# Gate_Drive.net
KiCad netlist of a schematic drawn in Altium Designer
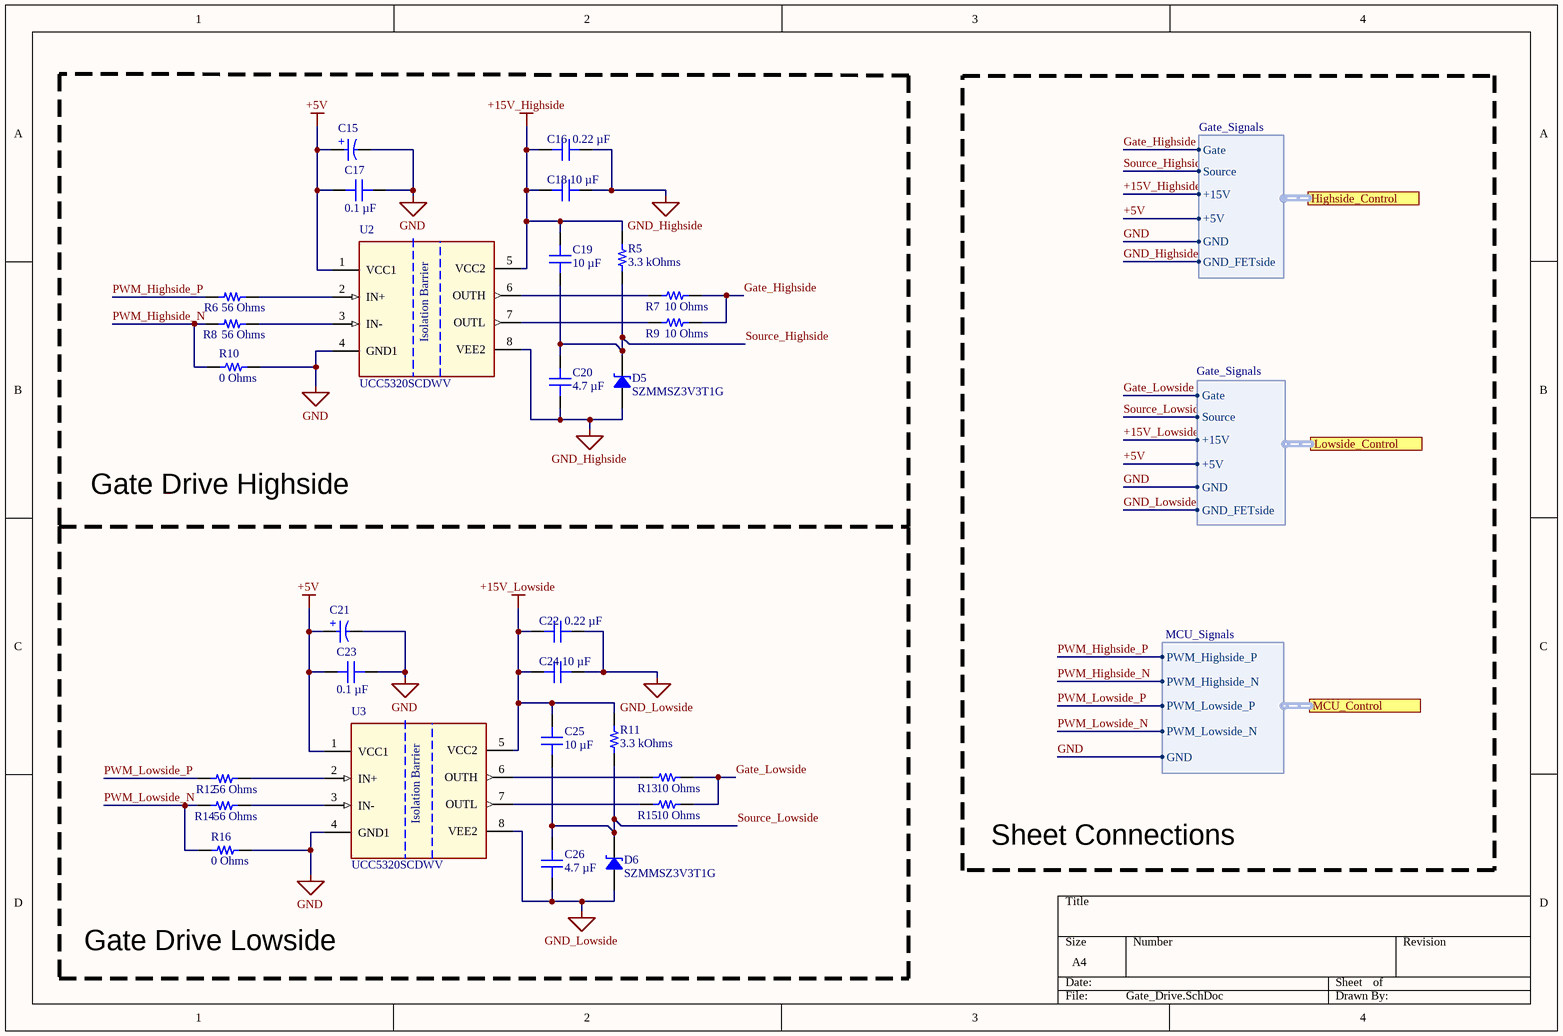
[diagram p0: Gate_Drive.SchDoc]

(export (version "E")
  (design (tool "Eeschema 10.0.6"))
  (components
    (comp (ref "C15")
      (value "1uF")
      (footprint "WCAP-ATG5_D5H11")
      (description "WCAP-ATG5 Aluminum Electrolytic Capacitor, Radial, THT, D5 x H11mm, 1µF, 50V")
      (fields
        (field (name "MANUFACTURER PART NUMBER") "860020672005")
        (field (name "MANUFACTURER") "Wurth Elektronik")
      )
      (libsource (lib "WE - Passive Components") (part "Capacitor_Polarized"))
    )
    (comp (ref "C16")
      (value "0.22 µF")
      (footprint "CAP 0805_2012")
      (description "CAP CER 0.22UF 25V X7R 0805")
      (fields
        (field (name "PART NUMBER") "VJ0805Y224KXXTW1BC")
        (field (name "MANUFACTURER") "Vishay Vitramon")
      )
      (libsource (lib "Celestial Altium Library - altium_library (2)") (part "Capacitor"))
    )
    (comp (ref "C17")
      (value "0.1 µF")
      (footprint "CAP 0805_2012")
      (description "CAP CER 0.1UF 50V X7R 0805")
      (fields (field (name "PART NUMBER") "VJ0805Y104MXAMR") (field (name "MANUFACTURER") "Vishay Vitramon"))
      (libsource (lib "Celestial Altium Library - altium_library (2)") (part "Capacitor"))
    )
    (comp (ref "C18")
      (value "10 µF")
      (footprint "CAP 0805_2012")
      (description "CAP CER 10UF 25V X6S 0805")
      (fields (field (name "PART NUMBER") "TMK212BC6106MG-T") (field (name "MANUFACTURER") "Taiyo Yuden"))
      (libsource (lib "Celestial Altium Library - altium_library (2)") (part "Capacitor"))
    )
    (comp (ref "C19")
      (value "10 µF")
      (footprint "CAP 0805_2012")
      (description "CAP CER 10UF 25V X6S 0805")
      (fields (field (name "PART NUMBER") "TMK212BC6106MG-T") (field (name "MANUFACTURER") "Taiyo Yuden"))
      (libsource (lib "Celestial Altium Library - altium_library (2)") (part "Capacitor"))
    )
    (comp (ref "C20")
      (value "4.7 µF")
      (footprint "CAP 0805_2012")
      (description "CAP CER 4.7UF 10V Y5V 0805")
      (fields
        (field (name "PART NUMBER") "VJ0805V475ZXQTW1BC")
        (field (name "MANUFACTURER") "Vishay Vitramon")
      )
      (libsource (lib "Celestial Altium Library - altium_library (2)") (part "Capacitor"))
    )
    (comp (ref "C21")
      (value "1uF")
      (footprint "WCAP-ATG5_D5H11")
      (description "WCAP-ATG5 Aluminum Electrolytic Capacitor, Radial, THT, D5 x H11mm, 1µF, 50V")
      (fields
        (field (name "MANUFACTURER PART NUMBER") "860020672005")
        (field (name "MANUFACTURER") "Wurth Elektronik")
      )
      (libsource (lib "WE - Passive Components") (part "Capacitor_Polarized"))
    )
    (comp (ref "C22")
      (value "0.22 µF")
      (footprint "CAP 0805_2012")
      (description "CAP CER 0.22UF 25V X7R 0805")
      (fields
        (field (name "PART NUMBER") "VJ0805Y224KXXTW1BC")
        (field (name "MANUFACTURER") "Vishay Vitramon")
      )
      (libsource (lib "Celestial Altium Library - altium_library (2)") (part "Capacitor"))
    )
    (comp (ref "C23")
      (value "0.1 µF")
      (footprint "CAP 0805_2012")
      (description "CAP CER 0.1UF 50V X7R 0805")
      (fields (field (name "PART NUMBER") "VJ0805Y104MXAMR") (field (name "MANUFACTURER") "Vishay Vitramon"))
      (libsource (lib "Celestial Altium Library - altium_library (2)") (part "Capacitor"))
    )
    (comp (ref "C24")
      (value "10 µF")
      (footprint "CAP 0805_2012")
      (description "CAP CER 10UF 25V X6S 0805")
      (fields (field (name "PART NUMBER") "TMK212BC6106MG-T") (field (name "MANUFACTURER") "Taiyo Yuden"))
      (libsource (lib "Celestial Altium Library - altium_library (2)") (part "Capacitor"))
    )
    (comp (ref "C25")
      (value "10 µF")
      (footprint "CAP 0805_2012")
      (description "CAP CER 10UF 25V X6S 0805")
      (fields (field (name "PART NUMBER") "TMK212BC6106MG-T") (field (name "MANUFACTURER") "Taiyo Yuden"))
      (libsource (lib "Celestial Altium Library - altium_library (2)") (part "Capacitor"))
    )
    (comp (ref "C26")
      (value "4.7 µF")
      (footprint "CAP 0805_2012")
      (description "CAP CER 4.7UF 10V Y5V 0805")
      (fields
        (field (name "PART NUMBER") "VJ0805V475ZXQTW1BC")
        (field (name "MANUFACTURER") "Vishay Vitramon")
      )
      (libsource (lib "Celestial Altium Library - altium_library (2)") (part "Capacitor"))
    )
    (comp (ref "D5")
      (value "SZMMSZ3V3T1G")
      (footprint "SOD-123")
      (description "DIODE ZENER 3.3V 500MW SOD123")
      (fields (field (name "MANUFACTURER") "ON Semiconductor") (field (name "TOLERANCE") "±5%"))
      (libsource (lib "Celestial Altium Library - altium_library (2)") (part "Diode Zener"))
    )
    (comp (ref "D6")
      (value "SZMMSZ3V3T1G")
      (footprint "SOD-123")
      (description "DIODE ZENER 3.3V 500MW SOD123")
      (fields (field (name "MANUFACTURER") "ON Semiconductor") (field (name "TOLERANCE") "±5%"))
      (libsource (lib "Celestial Altium Library - altium_library (2)") (part "Diode Zener"))
    )
    (comp (ref "R5")
      (value "3.3 kOhms")
      (footprint "RES 0805_2012")
      (description "RES SMD 3.3K OHM 0.1% 1/10W 0805")
      (fields
        (field (name "PART NUMBER") "CPF0805B3K3E1")
        (field (name "MANUFACTURER") "TE Connectivity Passive Product")
      )
      (libsource (lib "Celestial Altium Library - altium_library (2)") (part "Resistor"))
    )
    (comp (ref "R6")
      (value "56 Ohms")
      (footprint "RES 0805_2012")
      (description "3430 A2 1% 56R 100PPM 1K RL")
      (fields
        (field (name "PART NUMBER") "3430A2F56RTDF")
        (field (name "MANUFACTURER") "TE Connectivity Passive Product")
      )
      (libsource (lib "Celestial Altium Library - altium_library (2)") (part "Resistor"))
    )
    (comp (ref "R7")
      (value "10 Ohms")
      (footprint "RES 0805_2012")
      (description "3430 A2 1% 10R 100PPM 1K RL")
      (fields
        (field (name "PART NUMBER") "3430A2F10RTDF")
        (field (name "MANUFACTURER") "TE Connectivity Passive Product")
      )
      (libsource (lib "Celestial Altium Library - altium_library (2)") (part "Resistor"))
    )
    (comp (ref "R8")
      (value "56 Ohms")
      (footprint "RES 0805_2012")
      (description "3430 A2 1% 56R 100PPM 1K RL")
      (fields
        (field (name "PART NUMBER") "3430A2F56RTDF")
        (field (name "MANUFACTURER") "TE Connectivity Passive Product")
      )
      (libsource (lib "Celestial Altium Library - altium_library (2)") (part "Resistor"))
    )
    (comp (ref "R9")
      (value "10 Ohms")
      (footprint "RES 0805_2012")
      (description "3430 A2 1% 10R 100PPM 1K RL")
      (fields
        (field (name "PART NUMBER") "3430A2F10RTDF")
        (field (name "MANUFACTURER") "TE Connectivity Passive Product")
      )
      (libsource (lib "Celestial Altium Library - altium_library (2)") (part "Resistor"))
    )
    (comp (ref "R10")
      (value "0 Ohms")
      (footprint "RES 0805_2012")
      (description "RES SMD 0 OHM JUMPER 1/2W 0805")
      (fields (field (name "PART NUMBER") "5106") (field (name "MANUFACTURER") "Keystone Electronics"))
      (libsource (lib "Celestial Altium Library - altium_library (2)") (part "Resistor"))
    )
    (comp (ref "R11")
      (value "3.3 kOhms")
      (footprint "RES 0805_2012")
      (description "RES SMD 3.3K OHM 0.1% 1/10W 0805")
      (fields
        (field (name "PART NUMBER") "CPF0805B3K3E1")
        (field (name "MANUFACTURER") "TE Connectivity Passive Product")
      )
      (libsource (lib "Celestial Altium Library - altium_library (2)") (part "Resistor"))
    )
    (comp (ref "R12")
      (value "56 Ohms")
      (footprint "RES 0805_2012")
      (description "3430 A2 1% 56R 100PPM 1K RL")
      (fields
        (field (name "PART NUMBER") "3430A2F56RTDF")
        (field (name "MANUFACTURER") "TE Connectivity Passive Product")
      )
      (libsource (lib "Celestial Altium Library - altium_library (2)") (part "Resistor"))
    )
    (comp (ref "R13")
      (value "10 Ohms")
      (footprint "RES 0805_2012")
      (description "3430 A2 1% 10R 100PPM 1K RL")
      (fields
        (field (name "PART NUMBER") "3430A2F10RTDF")
        (field (name "MANUFACTURER") "TE Connectivity Passive Product")
      )
      (libsource (lib "Celestial Altium Library - altium_library (2)") (part "Resistor"))
    )
    (comp (ref "R14")
      (value "56 Ohms")
      (footprint "RES 0805_2012")
      (description "3430 A2 1% 56R 100PPM 1K RL")
      (fields
        (field (name "PART NUMBER") "3430A2F56RTDF")
        (field (name "MANUFACTURER") "TE Connectivity Passive Product")
      )
      (libsource (lib "Celestial Altium Library - altium_library (2)") (part "Resistor"))
    )
    (comp (ref "R15")
      (value "10 Ohms")
      (footprint "RES 0805_2012")
      (description "3430 A2 1% 10R 100PPM 1K RL")
      (fields
        (field (name "PART NUMBER") "3430A2F10RTDF")
        (field (name "MANUFACTURER") "TE Connectivity Passive Product")
      )
      (libsource (lib "Celestial Altium Library - altium_library (2)") (part "Resistor"))
    )
    (comp (ref "R16")
      (value "0 Ohms")
      (footprint "RES 0805_2012")
      (description "RES SMD 0 OHM JUMPER 1/2W 0805")
      (fields (field (name "PART NUMBER") "5106") (field (name "MANUFACTURER") "Keystone Electronics"))
      (libsource (lib "Celestial Altium Library - altium_library (2)") (part "Resistor"))
    )
    (comp (ref "U2")
      (value "UCC5320SCDWV")
      (footprint "DWV0008A")
      (fields (field (name "COPYRIGHT") "Copyright (C) 2025 Ultra Librarian. All rights reserved."))
      (libsource (lib "Schlib1") (part "UCC5320SCDWV"))
    )
    (comp (ref "U3")
      (value "UCC5320SCDWV")
      (footprint "DWV0008A")
      (fields (field (name "COPYRIGHT") "Copyright (C) 2025 Ultra Librarian. All rights reserved."))
      (libsource (lib "Schlib1") (part "UCC5320SCDWV"))
    )
  )
  (nets
    (net (code "3") (name "+5V") (class "Default")
      (node (ref "C15") (pin "1") (pinfunction "P_1") (pintype "passive"))
      (node (ref "C17") (pin "1") (pinfunction "1_1") (pintype "passive"))
      (node (ref "C21") (pin "1") (pinfunction "P_1") (pintype "passive"))
      (node (ref "C23") (pin "1") (pinfunction "1_1") (pintype "passive"))
      (node (ref "U2") (pin "1") (pinfunction "VCC1_1") (pintype "power_in"))
      (node (ref "U3") (pin "1") (pinfunction "VCC1_1") (pintype "power_in"))
    )
    (net (code "4") (name "+15V_Highside") (class "Default")
      (node (ref "C16") (pin "1") (pinfunction "1_1") (pintype "passive"))
      (node (ref "C18") (pin "2") (pinfunction "2_2") (pintype "passive"))
      (node (ref "C19") (pin "2") (pinfunction "2_2") (pintype "passive"))
      (node (ref "R5") (pin "2") (pinfunction "2_2") (pintype "passive"))
      (node (ref "U2") (pin "5") (pinfunction "VCC2_5") (pintype "power_in"))
    )
    (net (code "5") (name "+15V_Lowside") (class "Default")
      (node (ref "C22") (pin "1") (pinfunction "1_1") (pintype "passive"))
      (node (ref "C24") (pin "2") (pinfunction "2_2") (pintype "passive"))
      (node (ref "C25") (pin "2") (pinfunction "2_2") (pintype "passive"))
      (node (ref "R11") (pin "2") (pinfunction "2_2") (pintype "passive"))
      (node (ref "U3") (pin "5") (pinfunction "VCC2_5") (pintype "power_in"))
    )
    (net (code "6") (name "/Gate_Highside") (class "Default")
      (node (ref "R7") (pin "2") (pinfunction "2_2") (pintype "passive"))
      (node (ref "R9") (pin "2") (pinfunction "2_2") (pintype "passive"))
    )
    (net (code "7") (name "/Gate_Lowside") (class "Default")
      (node (ref "R13") (pin "2") (pinfunction "2_2") (pintype "passive"))
      (node (ref "R15") (pin "2") (pinfunction "2_2") (pintype "passive"))
    )
    (net (code "8") (name "/PWM_Highside_N") (class "Default")
      (node (ref "R10") (pin "1") (pinfunction "1_1") (pintype "passive"))
      (node (ref "R8") (pin "1") (pinfunction "1_1") (pintype "passive"))
    )
    (net (code "9") (name "/PWM_Highside_P") (class "Default")
      (node (ref "R6") (pin "1") (pinfunction "1_1") (pintype "passive"))
    )
    (net (code "10") (name "/PWM_Lowside_N") (class "Default")
      (node (ref "R14") (pin "1") (pinfunction "1_1") (pintype "passive"))
      (node (ref "R16") (pin "1") (pinfunction "1_1") (pintype "passive"))
    )
    (net (code "11") (name "/PWM_Lowside_P") (class "Default")
      (node (ref "R12") (pin "1") (pinfunction "1_1") (pintype "passive"))
    )
    (net (code "12") (name "/Source_Highside") (class "Default")
      (node (ref "C19") (pin "1") (pinfunction "1_1") (pintype "passive"))
      (node (ref "C20") (pin "2") (pinfunction "2_2") (pintype "passive"))
      (node (ref "D5") (pin "2") (pinfunction "2_2") (pintype "passive"))
      (node (ref "R5") (pin "1") (pinfunction "1_1") (pintype "passive"))
    )
    (net (code "13") (name "/Source_Lowside") (class "Default")
      (node (ref "C25") (pin "1") (pinfunction "1_1") (pintype "passive"))
      (node (ref "C26") (pin "2") (pinfunction "2_2") (pintype "passive"))
      (node (ref "D6") (pin "2") (pinfunction "2_2") (pintype "passive"))
      (node (ref "R11") (pin "1") (pinfunction "1_1") (pintype "passive"))
    )
    (net (code "16") (name "GND") (class "Default")
      (node (ref "C15") (pin "2") (pinfunction "N_2") (pintype "passive"))
      (node (ref "C17") (pin "2") (pinfunction "2_2") (pintype "passive"))
      (node (ref "C21") (pin "2") (pinfunction "N_2") (pintype "passive"))
      (node (ref "C23") (pin "2") (pinfunction "2_2") (pintype "passive"))
      (node (ref "R10") (pin "2") (pinfunction "2_2") (pintype "passive"))
      (node (ref "R16") (pin "2") (pinfunction "2_2") (pintype "passive"))
      (node (ref "U2") (pin "4") (pinfunction "GND1_4") (pintype "power_in"))
      (node (ref "U3") (pin "4") (pinfunction "GND1_4") (pintype "power_in"))
    )
    (net (code "17") (name "GND_Highside") (class "Default")
      (node (ref "C16") (pin "2") (pinfunction "2_2") (pintype "passive"))
      (node (ref "C18") (pin "1") (pinfunction "1_1") (pintype "passive"))
      (node (ref "C20") (pin "1") (pinfunction "1_1") (pintype "passive"))
      (node (ref "D5") (pin "1") (pinfunction "1_1") (pintype "passive"))
      (node (ref "U2") (pin "8") (pinfunction "VEE2_8") (pintype "power_in"))
    )
    (net (code "18") (name "GND_Lowside") (class "Default")
      (node (ref "C22") (pin "2") (pinfunction "2_2") (pintype "passive"))
      (node (ref "C24") (pin "1") (pinfunction "1_1") (pintype "passive"))
      (node (ref "C26") (pin "1") (pinfunction "1_1") (pintype "passive"))
      (node (ref "D6") (pin "1") (pinfunction "1_1") (pintype "passive"))
      (node (ref "U3") (pin "8") (pinfunction "VEE2_8") (pintype "power_in"))
    )
    (net (code "19") (name "Net-(U2-IN+)") (class "Default")
      (node (ref "R6") (pin "2") (pinfunction "2_2") (pintype "passive"))
      (node (ref "U2") (pin "2") (pinfunction "IN+_2") (pintype "input"))
    )
    (net (code "20") (name "Net-(U2-IN-)") (class "Default")
      (node (ref "R8") (pin "2") (pinfunction "2_2") (pintype "passive"))
      (node (ref "U2") (pin "3") (pinfunction "IN-_3") (pintype "input"))
    )
    (net (code "21") (name "Net-(U2-OUTH)") (class "Default")
      (node (ref "R7") (pin "1") (pinfunction "1_1") (pintype "passive"))
      (node (ref "U2") (pin "6") (pinfunction "OUTH_6") (pintype "output"))
    )
    (net (code "22") (name "Net-(U2-OUTL)") (class "Default")
      (node (ref "R9") (pin "1") (pinfunction "1_1") (pintype "passive"))
      (node (ref "U2") (pin "7") (pinfunction "OUTL_7") (pintype "output"))
    )
    (net (code "23") (name "Net-(U3-IN+)") (class "Default")
      (node (ref "R12") (pin "2") (pinfunction "2_2") (pintype "passive"))
      (node (ref "U3") (pin "2") (pinfunction "IN+_2") (pintype "input"))
    )
    (net (code "24") (name "Net-(U3-IN-)") (class "Default")
      (node (ref "R14") (pin "2") (pinfunction "2_2") (pintype "passive"))
      (node (ref "U3") (pin "3") (pinfunction "IN-_3") (pintype "input"))
    )
    (net (code "25") (name "Net-(U3-OUTH)") (class "Default")
      (node (ref "R13") (pin "1") (pinfunction "1_1") (pintype "passive"))
      (node (ref "U3") (pin "6") (pinfunction "OUTH_6") (pintype "output"))
    )
    (net (code "26") (name "Net-(U3-OUTL)") (class "Default")
      (node (ref "R15") (pin "1") (pinfunction "1_1") (pintype "passive"))
      (node (ref "U3") (pin "7") (pinfunction "OUTL_7") (pintype "output"))
    )
  )
)
